# Schematic_v22.net
KiCad netlist of a schematic drawn in EAGLE
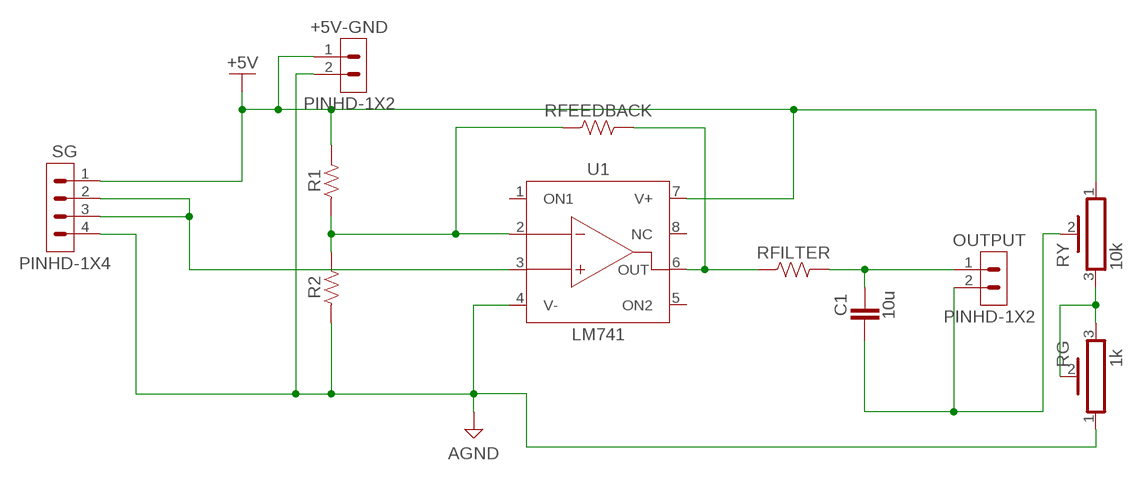
[diagram p0: schematic, sheet 1]

(export (version "E")
  (design (tool "Eeschema 10.0.6"))
  (components
    (comp (ref "+5V-GND")
      (value "PINHD-1X2")
      (footprint "eagle-import:1X02")
      (libsource (lib "eagle-import") (part "PINHD-1X2"))
    )
    (comp (ref "C1")
      (value "10u")
      (footprint "eagle-import:CAP-THRU-2.54MM")
      (libsource (lib "eagle-import") (part "CAPACITORCERAMIC-2.54MM"))
    )
    (comp (ref "OUTPUT")
      (value "PINHD-1X2")
      (footprint "eagle-import:1X02")
      (libsource (lib "eagle-import") (part "PINHD-1X2"))
    )
    (comp (ref "R1")
      (value "1k")
      (footprint "eagle-import:RESAD724W46L381D178B")
      (libsource (lib "eagle-import") (part "R-USAXIAL-7.2MM-PITCH_"))
    )
    (comp (ref "R2")
      (value "1k")
      (footprint "eagle-import:RESAD724W46L381D178B")
      (libsource (lib "eagle-import") (part "R-USAXIAL-7.2MM-PITCH_"))
    )
    (comp (ref "RFEEDBACK")
      (value "24M")
      (footprint "eagle-import:RESAD724W46L381D178B")
      (libsource (lib "eagle-import") (part "R-USAXIAL-7.2MM-PITCH_"))
    )
    (comp (ref "RFILTER")
      (value "47k")
      (footprint "eagle-import:RESAD724W46L381D178B")
      (libsource (lib "eagle-import") (part "R-USAXIAL-7.2MM-PITCH_"))
    )
    (comp (ref "RG")
      (value "1k")
      (footprint "eagle-import:HA-06-SM065")
      (libsource (lib "eagle-import") (part "POT_HA-06"))
    )
    (comp (ref "RY")
      (value "10k")
      (footprint "eagle-import:HA-06-SM065")
      (libsource (lib "eagle-import") (part "POT_HA-06"))
    )
    (comp (ref "SG")
      (value "PINHD-1X4")
      (footprint "eagle-import:1X04")
      (libsource (lib "eagle-import") (part "PINHD-1X4"))
    )
    (comp (ref "U1")
      (value "LM741")
      (footprint "eagle-import:DIP826W53P254L959H508Q8B")
      (libsource (lib "eagle-import") (part "LM741"))
    )
  )
  (nets
    (net (code "1") (name "+5V") (class "Default")
      (node (ref "+5V-GND") (pin "1") (pinfunction "1_1") (pintype "passive"))
      (node (ref "R1") (pin "2") (pinfunction "2_2") (pintype "passive"))
      (node (ref "RY") (pin "1") (pinfunction "P$1_1") (pintype "passive"))
      (node (ref "SG") (pin "1") (pinfunction "1_1") (pintype "passive"))
      (node (ref "U1") (pin "7") (pinfunction "V+_7") (pintype "bidirectional"))
    )
    (net (code "2") (name "AGND") (class "Default")
      (node (ref "+5V-GND") (pin "2") (pinfunction "2_2") (pintype "passive"))
      (node (ref "R2") (pin "1") (pinfunction "1_1") (pintype "passive"))
      (node (ref "RG") (pin "1") (pinfunction "P$1_1") (pintype "passive"))
      (node (ref "SG") (pin "4") (pinfunction "4_4") (pintype "passive"))
      (node (ref "U1") (pin "4") (pinfunction "V-_4") (pintype "bidirectional"))
    )
    (net (code "3") (name "Net-(C1-Pad1)") (class "Default")
      (node (ref "C1") (pin "1") (pinfunction "1_1") (pintype "passive"))
      (node (ref "OUTPUT") (pin "1") (pinfunction "1_1") (pintype "passive"))
      (node (ref "RFILTER") (pin "2") (pinfunction "2_2") (pintype "passive"))
    )
    (net (code "4") (name "Net-(RG-P$2)") (class "Default")
      (node (ref "RG") (pin "2") (pinfunction "P$2_2") (pintype "passive"))
      (node (ref "RG") (pin "3") (pinfunction "P$3_3") (pintype "passive"))
      (node (ref "RY") (pin "3") (pinfunction "P$3_3") (pintype "passive"))
    )
    (net (code "5") (name "Net-(RY-P$2)") (class "Default")
      (node (ref "C1") (pin "2") (pinfunction "2_2") (pintype "passive"))
      (node (ref "OUTPUT") (pin "2") (pinfunction "2_2") (pintype "passive"))
      (node (ref "RY") (pin "2") (pinfunction "P$2_2") (pintype "passive"))
    )
    (net (code "6") (name "Net-(U1-+IN)") (class "Default")
      (node (ref "SG") (pin "2") (pinfunction "2_2") (pintype "passive"))
      (node (ref "SG") (pin "3") (pinfunction "3_3") (pintype "passive"))
      (node (ref "U1") (pin "3") (pinfunction "+IN_3") (pintype "input"))
    )
    (net (code "7") (name "Net-(U1--IN)") (class "Default")
      (node (ref "R1") (pin "1") (pinfunction "1_1") (pintype "passive"))
      (node (ref "R2") (pin "2") (pinfunction "2_2") (pintype "passive"))
      (node (ref "RFEEDBACK") (pin "1") (pinfunction "1_1") (pintype "passive"))
      (node (ref "U1") (pin "2") (pinfunction "-IN_2") (pintype "input"))
    )
    (net (code "8") (name "Net-(U1-OUT)") (class "Default")
      (node (ref "RFEEDBACK") (pin "2") (pinfunction "2_2") (pintype "passive"))
      (node (ref "RFILTER") (pin "1") (pinfunction "1_1") (pintype "passive"))
      (node (ref "U1") (pin "6") (pinfunction "OUT_6") (pintype "output"))
    )
    (net (code "9") (name "unconnected-(U1-NC-Pad8)") (class "Default")
      (node (ref "U1") (pin "8") (pinfunction "NC_8") (pintype "passive"))
    )
    (net (code "10") (name "unconnected-(U1-ON1-Pad1)") (class "Default")
      (node (ref "U1") (pin "1") (pinfunction "ON1_1") (pintype "passive"))
    )
    (net (code "11") (name "unconnected-(U1-ON2-Pad5)") (class "Default")
      (node (ref "U1") (pin "5") (pinfunction "ON2_5") (pintype "passive"))
    )
  )
)
